# SCH_Radar-System_2024-05-14.net
KiCad netlist of a schematic drawn in EasyEDA
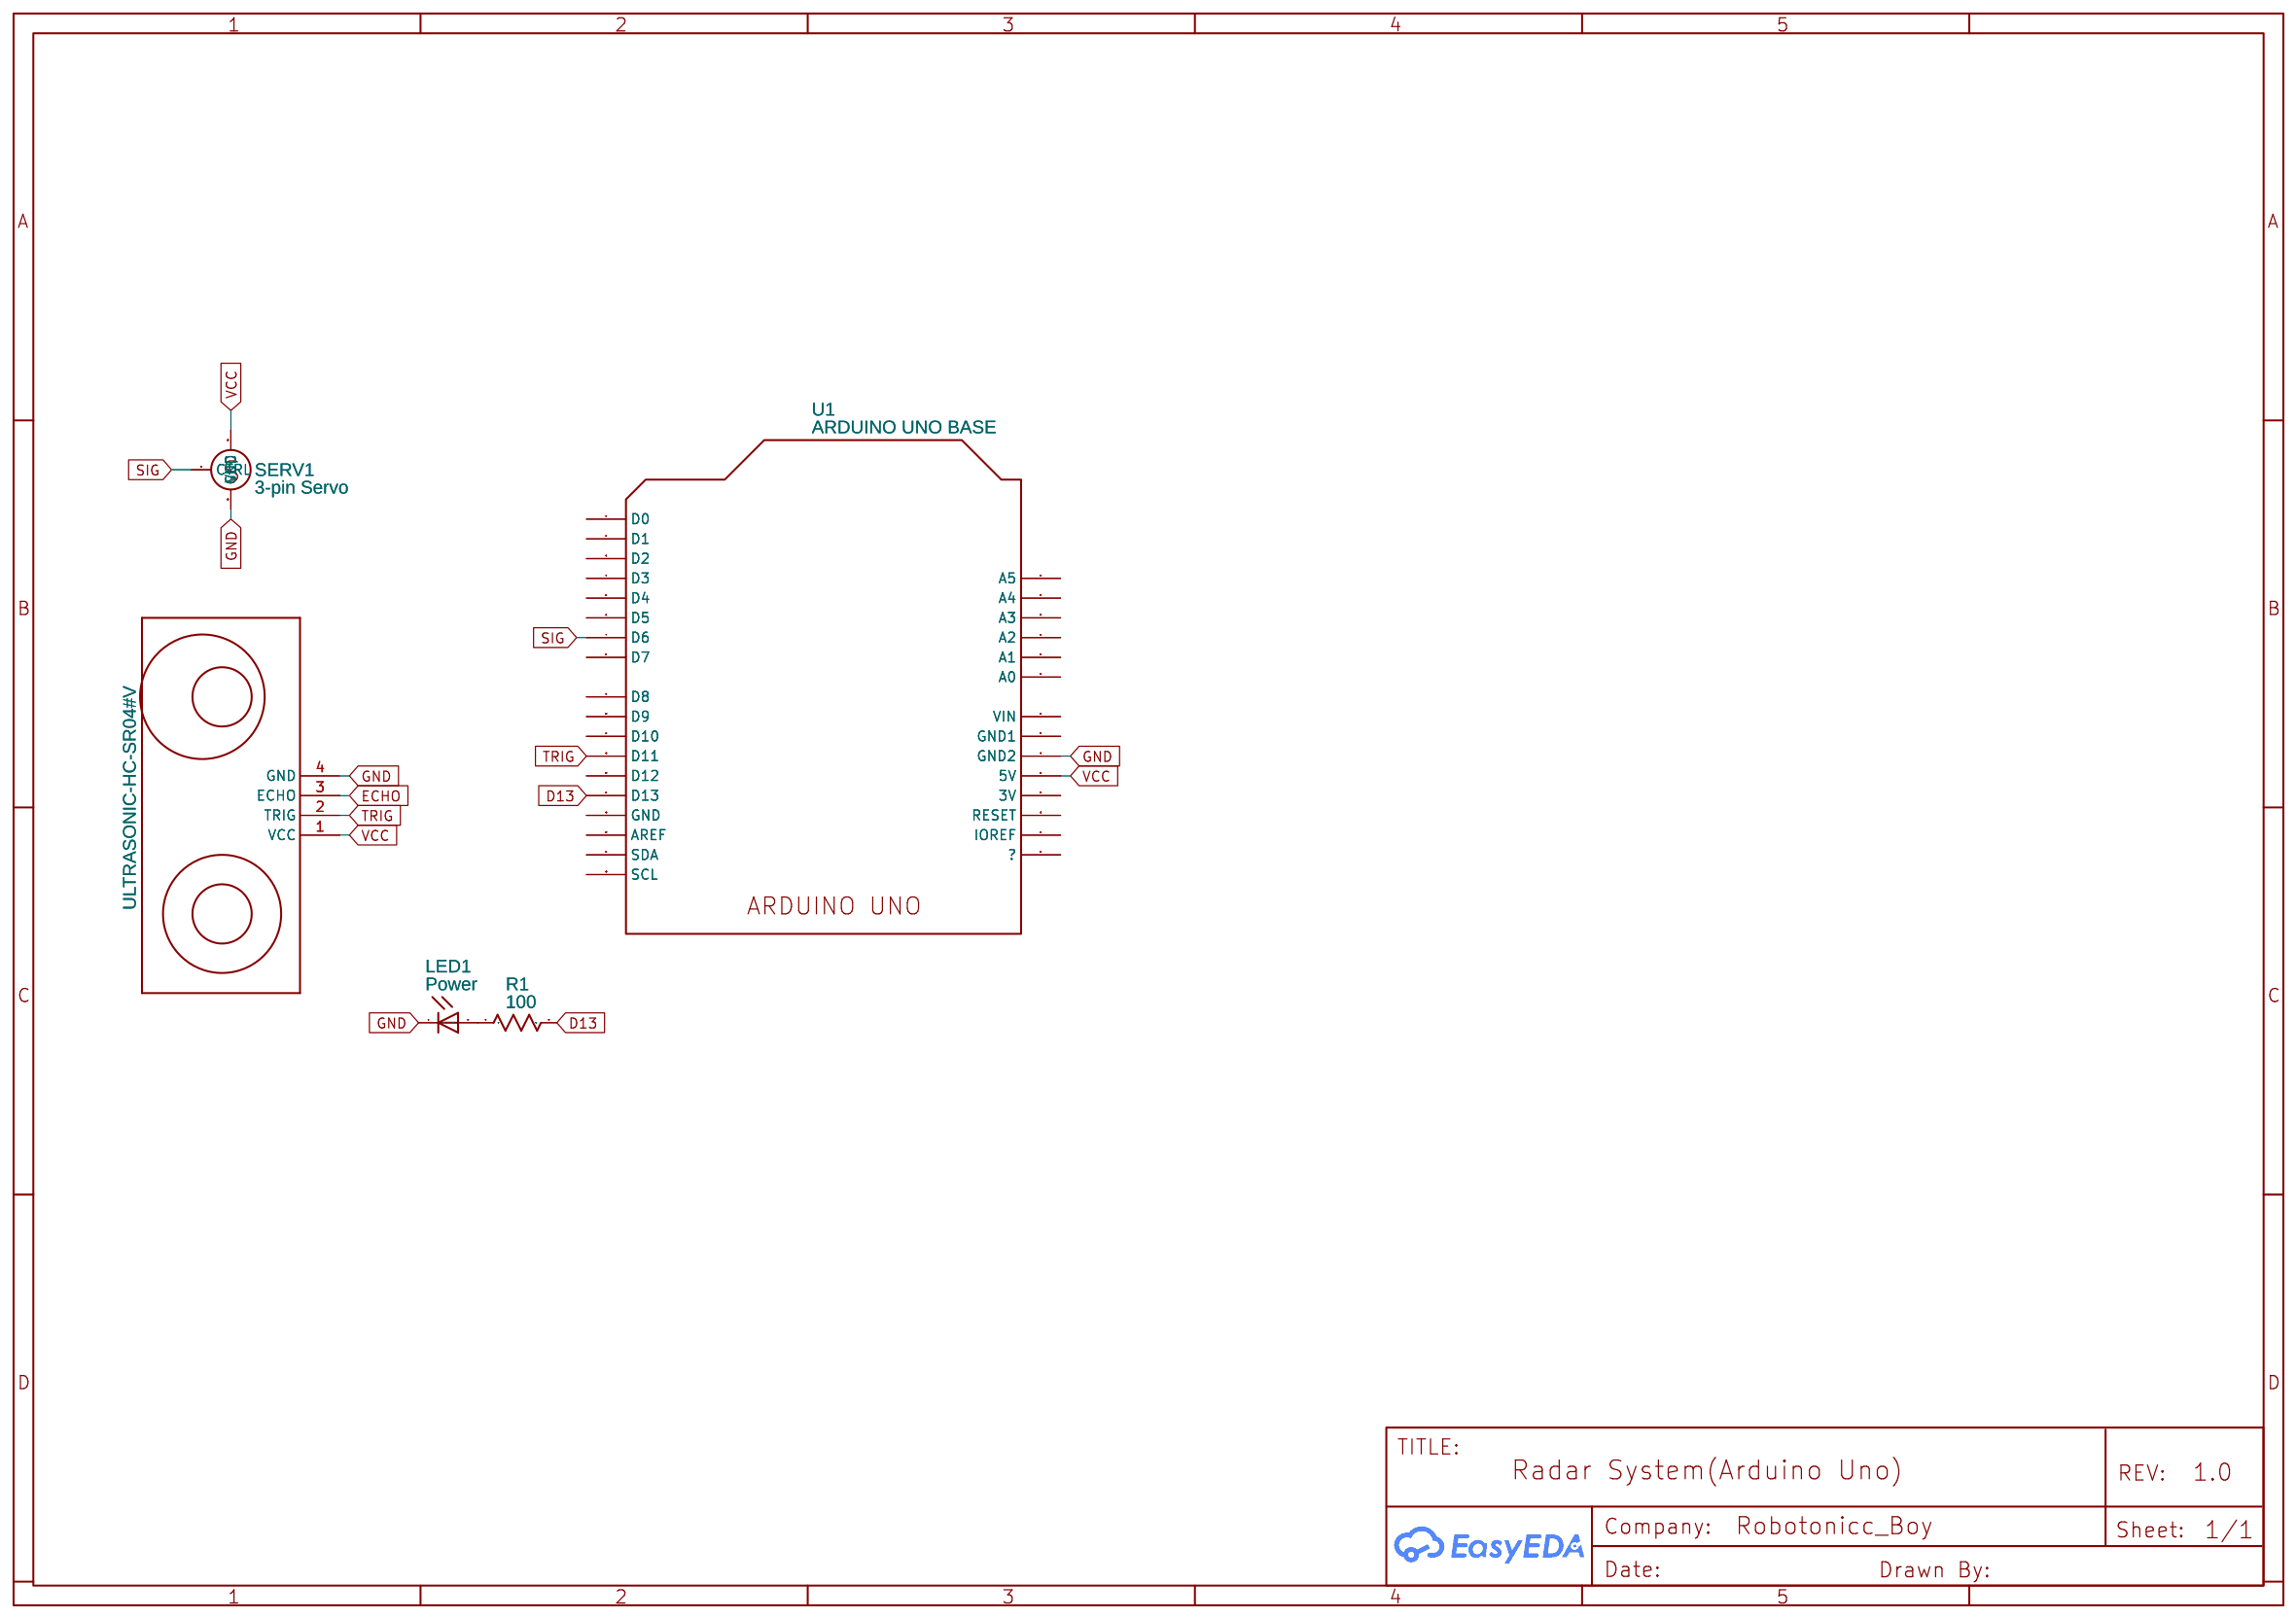
[diagram p0: Radar System Arduino Uno]
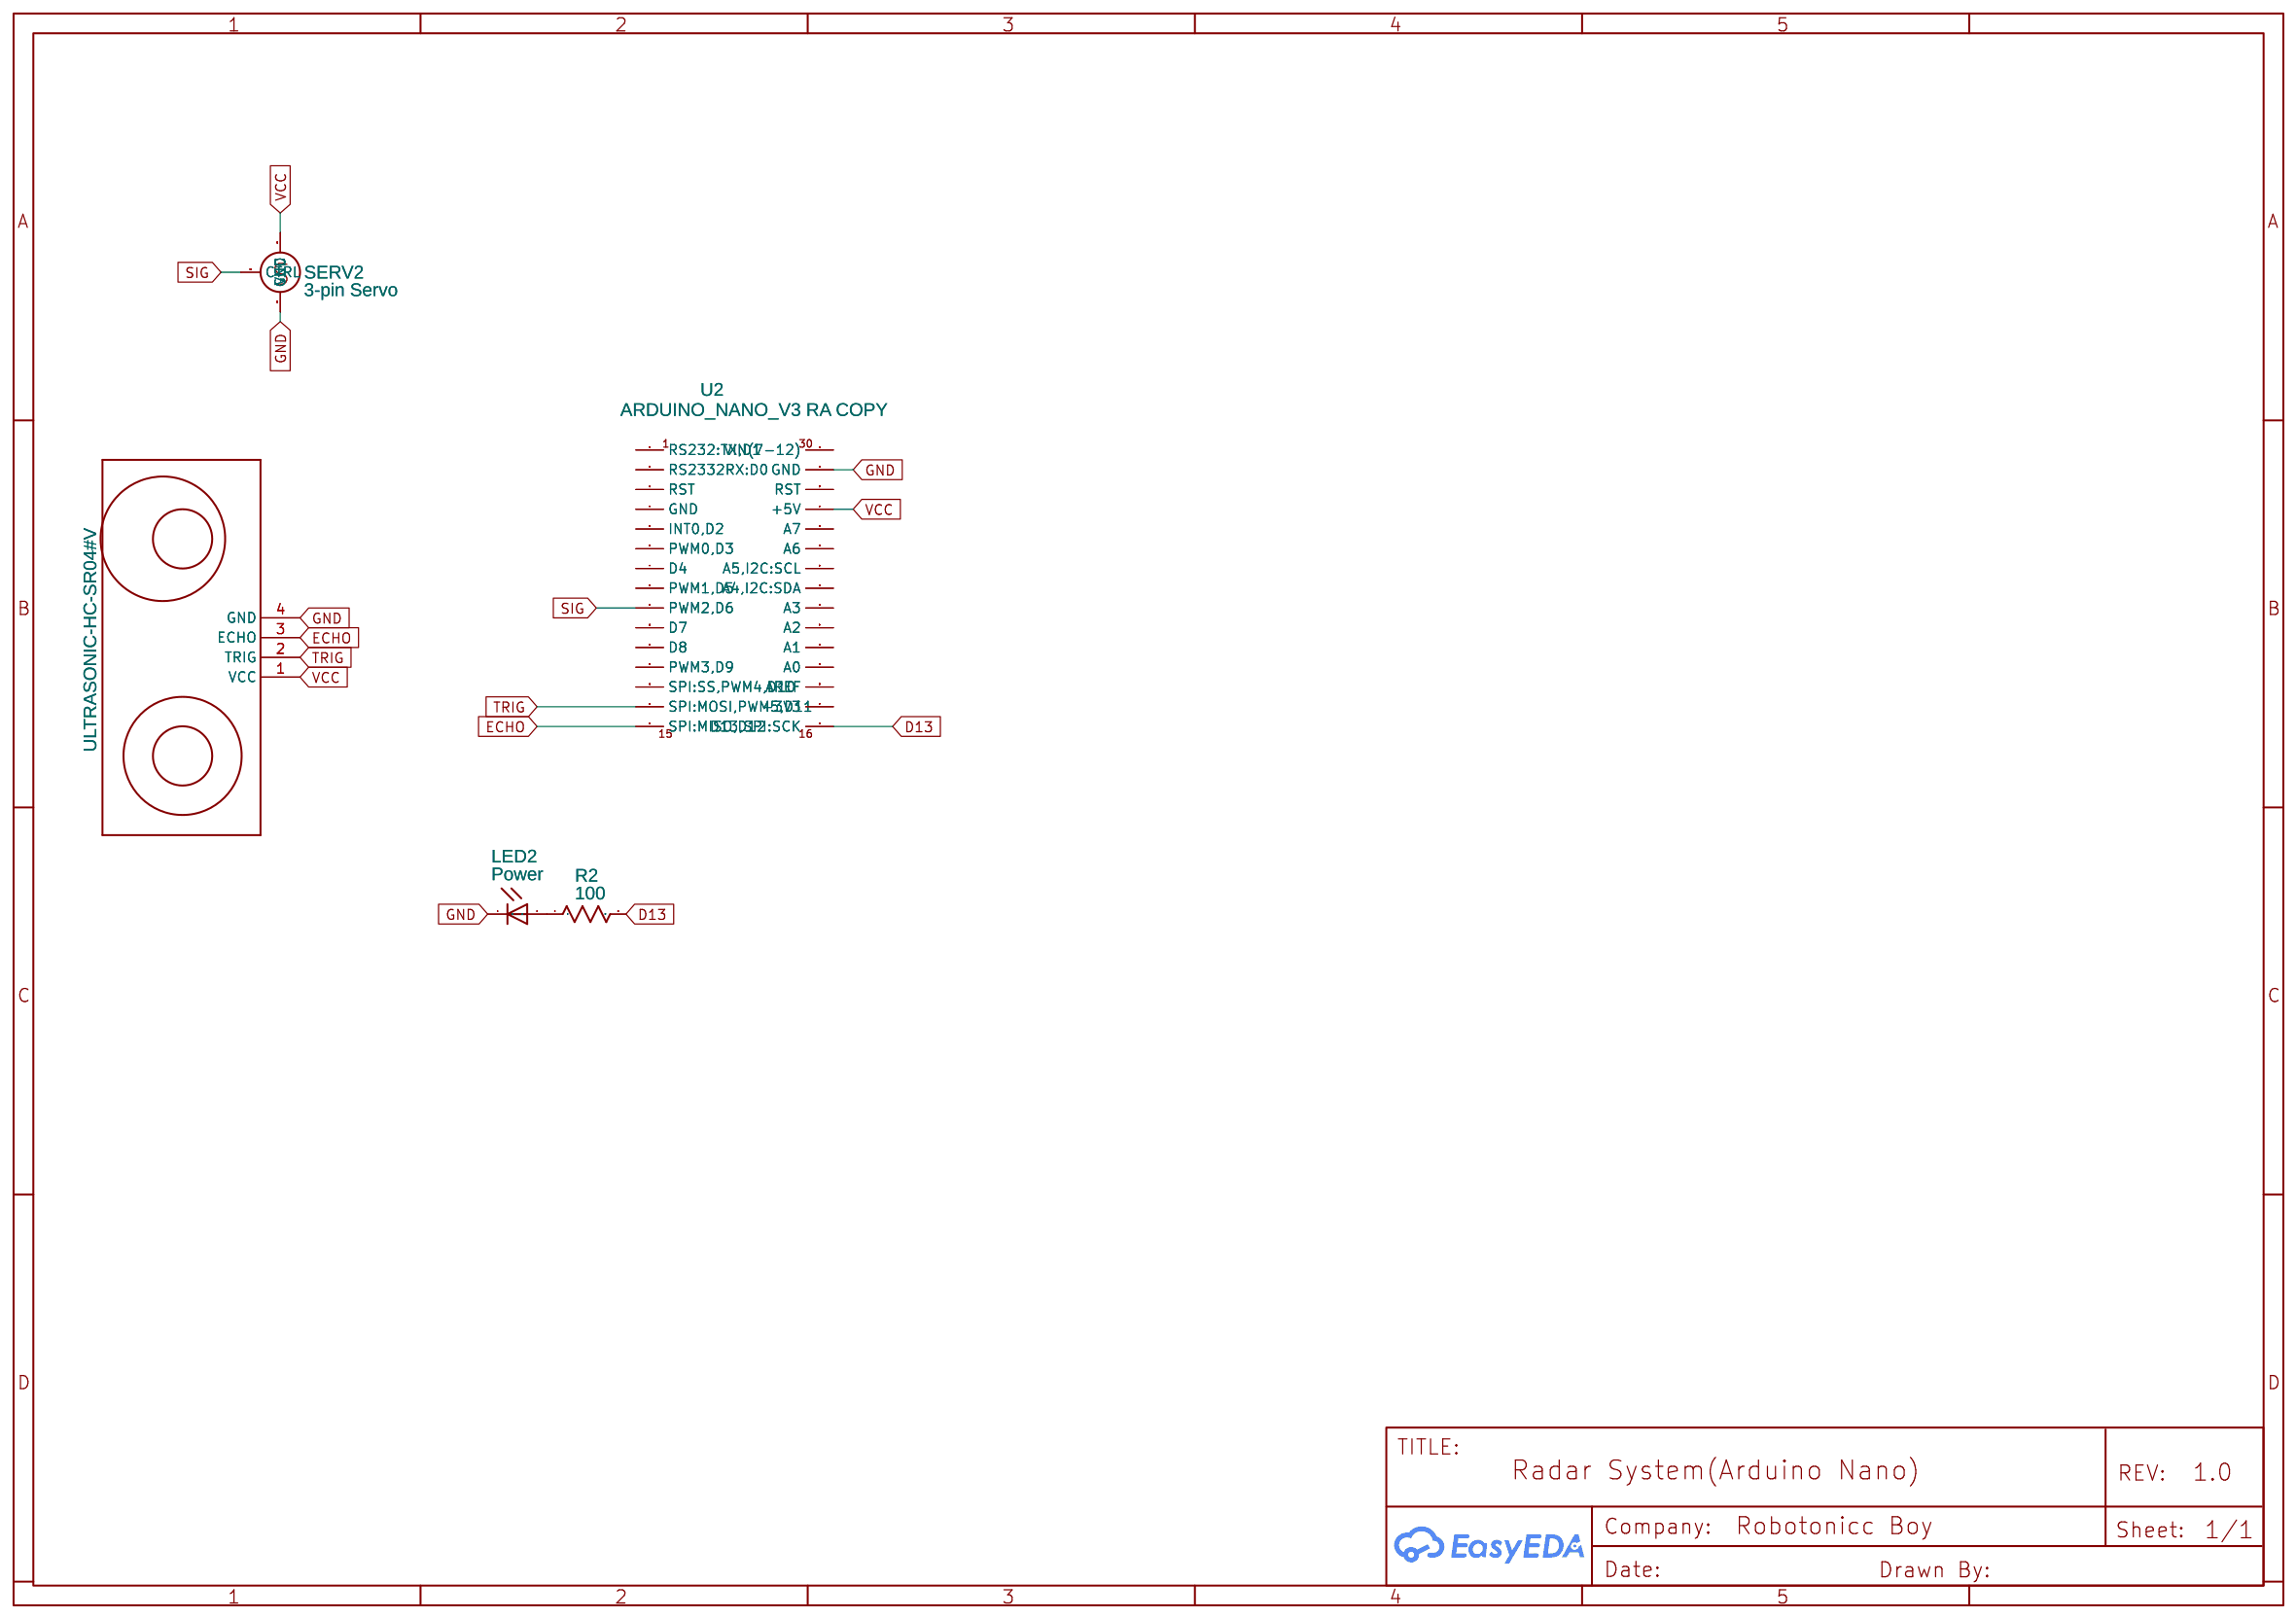
[diagram p1: Radar System Arduino Nano]

(export (version "E")
  (design (tool "Eeschema 10.0.6"))
  (components
    (comp (ref "1") (value "ULTRASONIC-HC-SR04#V") (libsource (lib "") (part "ULTRASONIC-HC-SR04#V")))
    (comp (ref "LED1") (value "Power") (libsource (lib "") (part "LED_LED5MM COPY2 COPY COPY")))
    (comp (ref "R1")
      (value "100")
      (fields (field (name "Manufacturer Part") "MCF 0.25W 100R") (field (name "Manufacturer") "MULTICOMP"))
      (libsource (lib "") (part "MCF 0.25W 100R"))
    )
    (comp (ref "SERV1") (value "3-pin Servo") (libsource (lib "") (part "3-pin Servo")))
    (comp (ref "U1") (value "ARDUINO UNO BASE") (libsource (lib "") (part "ARDUINO UNO BASE")))
    (comp (ref "2") (value "ULTRASONIC-HC-SR04#V") (libsource (lib "") (part "ULTRASONIC-HC-SR04#V")))
    (comp (ref "LED2") (value "Power") (libsource (lib "") (part "LED_LED5MM COPY2 COPY COPY")))
    (comp (ref "R2")
      (value "100")
      (fields (field (name "Manufacturer Part") "MCF 0.25W 100R") (field (name "Manufacturer") "MULTICOMP"))
      (libsource (lib "") (part "MCF 0.25W 100R"))
    )
    (comp (ref "SERV2") (value "3-pin Servo") (libsource (lib "") (part "3-pin Servo")))
    (comp (ref "U2")
      (value "ARDUINO_NANO_V3 RA COPY")
      (fields (field (name "Manufacturer Part") "Arduino Nano") (field (name "Manufacturer") "Arduino"))
      (libsource (lib "") (part "ARDUINO_NANO_V3 RA COPY"))
    )
  )
  (nets
    (net (code "1") (name "D13") (class "Default")
      (node (ref "R1") (pin "2") (pinfunction "2_2") (pintype "unspecified"))
      (node (ref "R2") (pin "2") (pinfunction "2_2") (pintype "unspecified"))
      (node (ref "U1") (pin "14") (pinfunction "D13_14") (pintype "unspecified"))
      (node (ref "U2") (pin "16") (pinfunction "D13,SPI:SCK_16") (pintype "unspecified"))
    )
    (net (code "2") (name "ECHO") (class "Default")
      (node (ref "1") (pin "3") (pinfunction "ECHO_3") (pintype "bidirectional"))
      (node (ref "2") (pin "3") (pinfunction "ECHO_3") (pintype "bidirectional"))
      (node (ref "U2") (pin "15") (pinfunction "SPI:MISO,D12_15") (pintype "unspecified"))
    )
    (net (code "3") (name "GND") (class "Default")
      (node (ref "1") (pin "4") (pinfunction "GND_4") (pintype "bidirectional"))
      (node (ref "2") (pin "4") (pinfunction "GND_4") (pintype "bidirectional"))
      (node (ref "LED1") (pin "K") (pinfunction "C_K") (pintype "unspecified"))
      (node (ref "LED2") (pin "K") (pinfunction "C_K") (pintype "unspecified"))
      (node (ref "SERV1") (pin "GND") (pinfunction "GND_GND") (pintype "unspecified"))
      (node (ref "SERV2") (pin "GND") (pinfunction "GND_GND") (pintype "unspecified"))
      (node (ref "U1") (pin "27") (pinfunction "GND2_27") (pintype "passive"))
      (node (ref "U2") (pin "29") (pinfunction "GND_29") (pintype "unspecified"))
    )
    (net (code "4") (name "Net-(LED1-PadA)") (class "Default")
      (node (ref "LED1") (pin "A") (pinfunction "A_A") (pintype "unspecified"))
      (node (ref "R1") (pin "1") (pinfunction "1_1") (pintype "unspecified"))
    )
    (net (code "5") (name "Net-(LED2-PadA)") (class "Default")
      (node (ref "LED2") (pin "A") (pinfunction "A_A") (pintype "unspecified"))
      (node (ref "R2") (pin "1") (pinfunction "1_1") (pintype "unspecified"))
    )
    (net (code "6") (name "SIG") (class "Default")
      (node (ref "SERV1") (pin "CTRL") (pinfunction "CTRL_CTRL") (pintype "unspecified"))
      (node (ref "SERV2") (pin "CTRL") (pinfunction "CTRL_CTRL") (pintype "unspecified"))
      (node (ref "U1") (pin "7") (pinfunction "D6_7") (pintype "unspecified"))
      (node (ref "U2") (pin "9") (pinfunction "PWM2,D6_9") (pintype "unspecified"))
    )
    (net (code "7") (name "TRIG") (class "Default")
      (node (ref "1") (pin "2") (pinfunction "TRIG_2") (pintype "bidirectional"))
      (node (ref "2") (pin "2") (pinfunction "TRIG_2") (pintype "bidirectional"))
      (node (ref "U1") (pin "12") (pinfunction "D11_12") (pintype "unspecified"))
      (node (ref "U2") (pin "14") (pinfunction "SPI:MOSI,PWM5,D11_14") (pintype "unspecified"))
    )
    (net (code "8") (name "VCC") (class "Default")
      (node (ref "1") (pin "1") (pinfunction "VCC_1") (pintype "bidirectional"))
      (node (ref "2") (pin "1") (pinfunction "VCC_1") (pintype "bidirectional"))
      (node (ref "SERV1") (pin "VCC") (pinfunction "VCC_VCC") (pintype "unspecified"))
      (node (ref "SERV2") (pin "VCC") (pinfunction "VCC_VCC") (pintype "unspecified"))
      (node (ref "U1") (pin "28") (pinfunction "5V_28") (pintype "passive"))
      (node (ref "U2") (pin "27") (pinfunction "+5V_27") (pintype "unspecified"))
    )
    (net (code "9") (name "unconnected-(U1-3V-Pad29)") (class "Default")
      (node (ref "U1") (pin "29") (pinfunction "3V_29") (pintype "passive"))
    )
    (net (code "10") (name "unconnected-(U1-?-Pad32)") (class "Default")
      (node (ref "U1") (pin "32") (pinfunction "?_32") (pintype "unspecified"))
    )
    (net (code "11") (name "unconnected-(U1-A0-Pad24)") (class "Default")
      (node (ref "U1") (pin "24") (pinfunction "A0_24") (pintype "unspecified"))
    )
    (net (code "12") (name "unconnected-(U1-A1-Pad23)") (class "Default")
      (node (ref "U1") (pin "23") (pinfunction "A1_23") (pintype "unspecified"))
    )
    (net (code "13") (name "unconnected-(U1-A2-Pad22)") (class "Default")
      (node (ref "U1") (pin "22") (pinfunction "A2_22") (pintype "unspecified"))
    )
    (net (code "14") (name "unconnected-(U1-A3-Pad21)") (class "Default")
      (node (ref "U1") (pin "21") (pinfunction "A3_21") (pintype "unspecified"))
    )
    (net (code "15") (name "unconnected-(U1-A4-Pad20)") (class "Default")
      (node (ref "U1") (pin "20") (pinfunction "A4_20") (pintype "unspecified"))
    )
    (net (code "16") (name "unconnected-(U1-A5-Pad19)") (class "Default")
      (node (ref "U1") (pin "19") (pinfunction "A5_19") (pintype "unspecified"))
    )
    (net (code "17") (name "unconnected-(U1-AREF-Pad16)") (class "Default")
      (node (ref "U1") (pin "16") (pinfunction "AREF_16") (pintype "unspecified"))
    )
    (net (code "18") (name "unconnected-(U1-D0-Pad1)") (class "Default")
      (node (ref "U1") (pin "1") (pinfunction "D0_1") (pintype "unspecified"))
    )
    (net (code "19") (name "unconnected-(U1-D1-Pad2)") (class "Default")
      (node (ref "U1") (pin "2") (pinfunction "D1_2") (pintype "unspecified"))
    )
    (net (code "20") (name "unconnected-(U1-D2-Pad3)") (class "Default")
      (node (ref "U1") (pin "3") (pinfunction "D2_3") (pintype "unspecified"))
    )
    (net (code "21") (name "unconnected-(U1-D3-Pad4)") (class "Default")
      (node (ref "U1") (pin "4") (pinfunction "D3_4") (pintype "unspecified"))
    )
    (net (code "22") (name "unconnected-(U1-D4-Pad5)") (class "Default")
      (node (ref "U1") (pin "5") (pinfunction "D4_5") (pintype "unspecified"))
    )
    (net (code "23") (name "unconnected-(U1-D5-Pad6)") (class "Default")
      (node (ref "U1") (pin "6") (pinfunction "D5_6") (pintype "unspecified"))
    )
    (net (code "24") (name "unconnected-(U1-D7-Pad8)") (class "Default")
      (node (ref "U1") (pin "8") (pinfunction "D7_8") (pintype "unspecified"))
    )
    (net (code "25") (name "unconnected-(U1-D8-Pad9)") (class "Default")
      (node (ref "U1") (pin "9") (pinfunction "D8_9") (pintype "unspecified"))
    )
    (net (code "26") (name "unconnected-(U1-D9-Pad10)") (class "Default")
      (node (ref "U1") (pin "10") (pinfunction "D9_10") (pintype "unspecified"))
    )
    (net (code "27") (name "unconnected-(U1-D10-Pad11)") (class "Default")
      (node (ref "U1") (pin "11") (pinfunction "D10_11") (pintype "unspecified"))
    )
    (net (code "28") (name "unconnected-(U1-D12-Pad13)") (class "Default")
      (node (ref "U1") (pin "13") (pinfunction "D12_13") (pintype "unspecified"))
    )
    (net (code "29") (name "unconnected-(U1-GND-Pad15)") (class "Default")
      (node (ref "U1") (pin "15") (pinfunction "GND_15") (pintype "passive"))
    )
    (net (code "30") (name "unconnected-(U1-GND1-Pad26)") (class "Default")
      (node (ref "U1") (pin "26") (pinfunction "GND1_26") (pintype "passive"))
    )
    (net (code "31") (name "unconnected-(U1-IOREF-Pad31)") (class "Default")
      (node (ref "U1") (pin "31") (pinfunction "IOREF_31") (pintype "unspecified"))
    )
    (net (code "32") (name "unconnected-(U1-RESET-Pad30)") (class "Default")
      (node (ref "U1") (pin "30") (pinfunction "RESET_30") (pintype "unspecified"))
    )
    (net (code "33") (name "unconnected-(U1-SCL-Pad18)") (class "Default")
      (node (ref "U1") (pin "18") (pinfunction "SCL_18") (pintype "unspecified"))
    )
    (net (code "34") (name "unconnected-(U1-SDA-Pad17)") (class "Default")
      (node (ref "U1") (pin "17") (pinfunction "SDA_17") (pintype "unspecified"))
    )
    (net (code "35") (name "unconnected-(U1-VIN-Pad25)") (class "Default")
      (node (ref "U1") (pin "25") (pinfunction "VIN_25") (pintype "passive"))
    )
    (net (code "36") (name "unconnected-(U2-+3V3-Pad17)") (class "Default")
      (node (ref "U2") (pin "17") (pinfunction "+3V3_17") (pintype "unspecified"))
    )
    (net (code "37") (name "unconnected-(U2-A0-Pad19)") (class "Default")
      (node (ref "U2") (pin "19") (pinfunction "A0_19") (pintype "unspecified"))
    )
    (net (code "38") (name "unconnected-(U2-A1-Pad20)") (class "Default")
      (node (ref "U2") (pin "20") (pinfunction "A1_20") (pintype "unspecified"))
    )
    (net (code "39") (name "unconnected-(U2-A2-Pad21)") (class "Default")
      (node (ref "U2") (pin "21") (pinfunction "A2_21") (pintype "unspecified"))
    )
    (net (code "40") (name "unconnected-(U2-A3-Pad22)") (class "Default")
      (node (ref "U2") (pin "22") (pinfunction "A3_22") (pintype "unspecified"))
    )
    (net (code "41") (name "unconnected-(U2-A4,I2C:SDA-Pad23)") (class "Default")
      (node (ref "U2") (pin "23") (pinfunction "A4,I2C:SDA_23") (pintype "unspecified"))
    )
    (net (code "42") (name "unconnected-(U2-A5,I2C:SCL-Pad24)") (class "Default")
      (node (ref "U2") (pin "24") (pinfunction "A5,I2C:SCL_24") (pintype "unspecified"))
    )
    (net (code "43") (name "unconnected-(U2-A6-Pad25)") (class "Default")
      (node (ref "U2") (pin "25") (pinfunction "A6_25") (pintype "unspecified"))
    )
    (net (code "44") (name "unconnected-(U2-A7-Pad26)") (class "Default")
      (node (ref "U2") (pin "26") (pinfunction "A7_26") (pintype "unspecified"))
    )
    (net (code "45") (name "unconnected-(U2-AREF-Pad18)") (class "Default")
      (node (ref "U2") (pin "18") (pinfunction "AREF_18") (pintype "unspecified"))
    )
    (net (code "46") (name "unconnected-(U2-D4-Pad7)") (class "Default")
      (node (ref "U2") (pin "7") (pinfunction "D4_7") (pintype "unspecified"))
    )
    (net (code "47") (name "unconnected-(U2-D7-Pad10)") (class "Default")
      (node (ref "U2") (pin "10") (pinfunction "D7_10") (pintype "unspecified"))
    )
    (net (code "48") (name "unconnected-(U2-D8-Pad11)") (class "Default")
      (node (ref "U2") (pin "11") (pinfunction "D8_11") (pintype "unspecified"))
    )
    (net (code "49") (name "unconnected-(U2-GND-Pad4)") (class "Default")
      (node (ref "U2") (pin "4") (pinfunction "GND_4") (pintype "unspecified"))
    )
    (net (code "50") (name "unconnected-(U2-INT0,D2-Pad5)") (class "Default")
      (node (ref "U2") (pin "5") (pinfunction "INT0,D2_5") (pintype "unspecified"))
    )
    (net (code "51") (name "unconnected-(U2-PWM0,D3-Pad6)") (class "Default")
      (node (ref "U2") (pin "6") (pinfunction "PWM0,D3_6") (pintype "unspecified"))
    )
    (net (code "52") (name "unconnected-(U2-PWM1,D5-Pad8)") (class "Default")
      (node (ref "U2") (pin "8") (pinfunction "PWM1,D5_8") (pintype "unspecified"))
    )
    (net (code "53") (name "unconnected-(U2-PWM3,D9-Pad12)") (class "Default")
      (node (ref "U2") (pin "12") (pinfunction "PWM3,D9_12") (pintype "unspecified"))
    )
    (net (code "54") (name "unconnected-(U2-RS232:TX,D1-Pad1)") (class "Default")
      (node (ref "U2") (pin "1") (pinfunction "RS232:TX,D1_1") (pintype "unspecified"))
    )
    (net (code "55") (name "unconnected-(U2-RS2332RX:D0-Pad2)") (class "Default")
      (node (ref "U2") (pin "2") (pinfunction "RS2332RX:D0_2") (pintype "unspecified"))
    )
    (net (code "56") (name "unconnected-(U2-RST-Pad3)") (class "Default")
      (node (ref "U2") (pin "3") (pinfunction "RST_3") (pintype "unspecified"))
    )
    (net (code "57") (name "unconnected-(U2-RST-Pad28)") (class "Default")
      (node (ref "U2") (pin "28") (pinfunction "RST_28") (pintype "unspecified"))
    )
    (net (code "58") (name "unconnected-(U2-SPI:SS,PWM4,D10-Pad13)") (class "Default")
      (node (ref "U2") (pin "13") (pinfunction "SPI:SS,PWM4,D10_13") (pintype "unspecified"))
    )
    (net (code "59") (name "unconnected-(U2-VIN(7-12)-Pad30)") (class "Default")
      (node (ref "U2") (pin "30") (pinfunction "VIN(7-12)_30") (pintype "unspecified"))
    )
  )
)
